# Boost_Mini.net
KiCad netlist of a schematic drawn in EAGLE
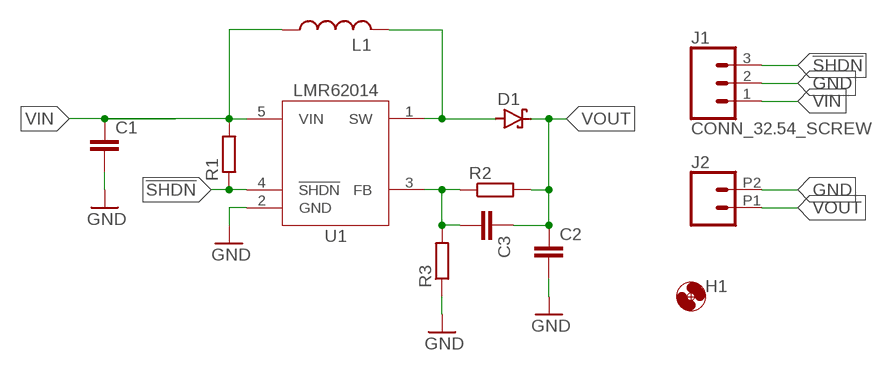
[diagram p0: schematic, sheet 1]

(export (version "E")
  (design (tool "Eeschema 10.0.6"))
  (components
    (comp (ref "C1")
      (value "C-EUC0805")
      (footprint "eagle-import:C0805")
      (libsource (lib "eagle-import") (part "C-EUC0805"))
    )
    (comp (ref "C2")
      (value "C-EUC0805")
      (footprint "eagle-import:C0805")
      (libsource (lib "eagle-import") (part "C-EUC0805"))
    )
    (comp (ref "C3")
      (value "C-EUC0603")
      (footprint "eagle-import:C0603")
      (libsource (lib "eagle-import") (part "C-EUC0603"))
    )
    (comp (ref "D1")
      (value "DIODE_SCHOTTKYDO-214AC")
      (footprint "eagle-import:DO214AC")
      (libsource (lib "eagle-import") (part "DIODE_SCHOTTKYDO-214AC"))
    )
    (comp (ref "H1")
      (value "MOUNTING_HOLE2_NP")
      (footprint "eagle-import:2_56")
      (libsource (lib "eagle-import") (part "MOUNTING_HOLE2_NP"))
    )
    (comp (ref "J1")
      (value "CONN_32.54_SCREW")
      (footprint "eagle-import:1X03_SCREW")
      (fields (field (name "MF") "On Shore") (field (name "MPN") "OSTVN03A150"))
      (libsource (lib "eagle-import") (part "CONN_32.54_SCREW"))
    )
    (comp (ref "J2")
      (value "CONN_022.54_SCREW_ROUND")
      (footprint "eagle-import:1X02_2.54_SCREWTERM_ROUND")
      (fields (field (name "MF") "OnShore") (field (name "MPN") "OSTVN02A150"))
      (libsource (lib "eagle-import") (part "CONN_022.54_SCREW_ROUND"))
    )
    (comp (ref "L1")
      (value "INDUCTORMAIA_4.1X4.1")
      (footprint "eagle-import:WE-MAIA(4.1X4.1)")
      (libsource (lib "eagle-import") (part "INDUCTORMAIA_4.1X4.1"))
    )
    (comp (ref "R1")
      (value "R-EU_R0603")
      (footprint "eagle-import:R0603")
      (fields (field (name "MF") "Yageo"))
      (libsource (lib "eagle-import") (part "R-EU_R0603"))
    )
    (comp (ref "R2")
      (value "R-EU_R0603")
      (footprint "eagle-import:R0603")
      (fields (field (name "MF") "Yageo"))
      (libsource (lib "eagle-import") (part "R-EU_R0603"))
    )
    (comp (ref "R3")
      (value "R-EU_R0603")
      (footprint "eagle-import:R0603")
      (fields (field (name "MF") "Yageo"))
      (libsource (lib "eagle-import") (part "R-EU_R0603"))
    )
    (comp (ref "U1")
      (value "LMR62014SOT23")
      (footprint "eagle-import:DBV0005A")
      (fields
        (field (name "DISP") "LMR62014")
        (field (name "MF") "TI")
        (field (name "MPN") "LMR62014XMF/NOPB")
      )
      (libsource (lib "eagle-import") (part "LMR62014SOT23"))
    )
  )
  (nets
    (net (code "1") (name "/~{SHDN}") (class "Default")
      (node (ref "J1") (pin "3") (pinfunction "3_3") (pintype "passive"))
      (node (ref "R1") (pin "1") (pinfunction "1_1") (pintype "passive"))
      (node (ref "U1") (pin "4") (pinfunction "~{SHDN}_4") (pintype "input"))
    )
    (net (code "2") (name "GND") (class "Default")
      (node (ref "C1") (pin "2") (pinfunction "2_2") (pintype "passive"))
      (node (ref "C2") (pin "2") (pinfunction "2_2") (pintype "passive"))
      (node (ref "J1") (pin "2") (pinfunction "2_2") (pintype "passive"))
      (node (ref "J2") (pin "P2") (pinfunction "2_P2") (pintype "passive"))
      (node (ref "R3") (pin "1") (pinfunction "1_1") (pintype "passive"))
      (node (ref "U1") (pin "2") (pinfunction "GND_2") (pintype "power_in"))
    )
    (net (code "3") (name "Net-(L1-2)") (class "Default")
      (node (ref "D1") (pin "A") (pinfunction "A_A") (pintype "passive"))
      (node (ref "L1") (pin "P$2") (pinfunction "2_P$2") (pintype "passive"))
      (node (ref "U1") (pin "1") (pinfunction "SW_1") (pintype "power_in"))
    )
    (net (code "4") (name "Net-(U1-FB)") (class "Default")
      (node (ref "C3") (pin "2") (pinfunction "2_2") (pintype "passive"))
      (node (ref "R2") (pin "1") (pinfunction "1_1") (pintype "passive"))
      (node (ref "R3") (pin "2") (pinfunction "2_2") (pintype "passive"))
      (node (ref "U1") (pin "3") (pinfunction "FB_3") (pintype "input"))
    )
    (net (code "5") (name "VIN") (class "Default")
      (node (ref "C1") (pin "1") (pinfunction "1_1") (pintype "passive"))
      (node (ref "J1") (pin "1") (pinfunction "1_1") (pintype "passive"))
      (node (ref "L1") (pin "P$1") (pinfunction "1_P$1") (pintype "passive"))
      (node (ref "R1") (pin "2") (pinfunction "2_2") (pintype "passive"))
      (node (ref "U1") (pin "5") (pinfunction "VIN_5") (pintype "power_in"))
    )
    (net (code "6") (name "VOUT") (class "Default")
      (node (ref "C2") (pin "1") (pinfunction "1_1") (pintype "passive"))
      (node (ref "C3") (pin "1") (pinfunction "1_1") (pintype "passive"))
      (node (ref "D1") (pin "C") (pinfunction "C_C") (pintype "passive"))
      (node (ref "J2") (pin "P1") (pinfunction "1_P1") (pintype "passive"))
      (node (ref "R2") (pin "2") (pinfunction "2_2") (pintype "passive"))
    )
  )
)
